# Sch.net
KiCad netlist of a schematic drawn in Altium Designer
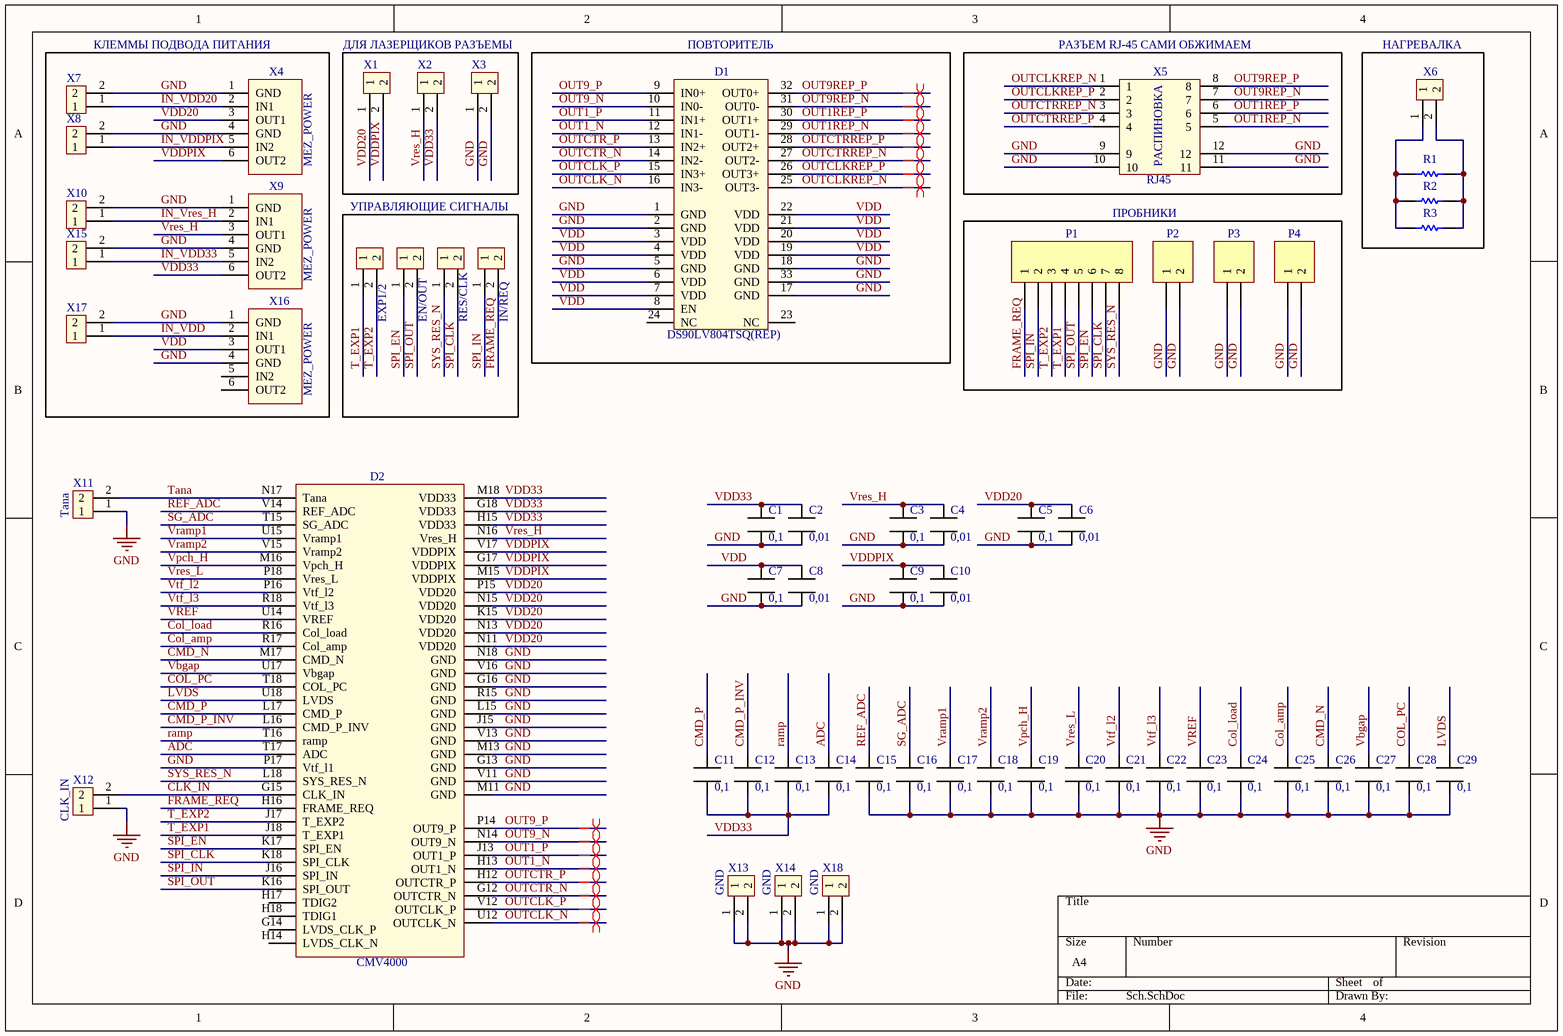
[diagram p0: Sch.SchDoc]

(export (version "E")
  (design (tool "Eeschema 10.0.6"))
  (components
    (comp (ref "C1") (value "0,1") (footprint "CAP_SMALL") (libsource (lib "Schlib") (part "CAP_SMALL")))
    (comp (ref "C2") (value "0,01") (footprint "CAP_SMALL") (libsource (lib "Schlib") (part "CAP_SMALL")))
    (comp (ref "C3") (value "0,1") (footprint "CAP_SMALL") (libsource (lib "Schlib") (part "CAP_SMALL")))
    (comp (ref "C4") (value "0,01") (footprint "CAP_SMALL") (libsource (lib "Schlib") (part "CAP_SMALL")))
    (comp (ref "C5") (value "0,1") (footprint "CAP_SMALL") (libsource (lib "Schlib") (part "CAP_SMALL")))
    (comp (ref "C6") (value "0,01") (footprint "CAP_SMALL") (libsource (lib "Schlib") (part "CAP_SMALL")))
    (comp (ref "C7") (value "0,1") (footprint "CAP_SMALL") (libsource (lib "Schlib") (part "CAP_SMALL")))
    (comp (ref "C8") (value "0,01") (footprint "CAP_SMALL") (libsource (lib "Schlib") (part "CAP_SMALL")))
    (comp (ref "C9") (value "0,1") (footprint "CAP_SMALL") (libsource (lib "Schlib") (part "CAP_SMALL")))
    (comp (ref "C10") (value "0,01") (footprint "CAP_SMALL") (libsource (lib "Schlib") (part "CAP_SMALL")))
    (comp (ref "C11") (value "0,1") (footprint "CAP_SMALL") (libsource (lib "Schlib") (part "CAP_SMALL")))
    (comp (ref "C12") (value "0,1") (footprint "CAP_SMALL") (libsource (lib "Schlib") (part "CAP_SMALL")))
    (comp (ref "C13") (value "0,1") (footprint "CAP_SMALL") (libsource (lib "Schlib") (part "CAP_SMALL")))
    (comp (ref "C14") (value "0,1") (footprint "CAP_SMALL") (libsource (lib "Schlib") (part "CAP_SMALL")))
    (comp (ref "C15") (value "0,1") (footprint "CAP_SMALL") (libsource (lib "Schlib") (part "CAP_SMALL")))
    (comp (ref "C16") (value "0,1") (footprint "CAP_SMALL") (libsource (lib "Schlib") (part "CAP_SMALL")))
    (comp (ref "C17") (value "0,1") (footprint "CAP_SMALL") (libsource (lib "Schlib") (part "CAP_SMALL")))
    (comp (ref "C18") (value "0,1") (footprint "CAP_SMALL") (libsource (lib "Schlib") (part "CAP_SMALL")))
    (comp (ref "C19") (value "0,1") (footprint "CAP_SMALL") (libsource (lib "Schlib") (part "CAP_SMALL")))
    (comp (ref "C20") (value "0,1") (footprint "CAP_SMALL") (libsource (lib "Schlib") (part "CAP_SMALL")))
    (comp (ref "C21") (value "0,1") (footprint "CAP_SMALL") (libsource (lib "Schlib") (part "CAP_SMALL")))
    (comp (ref "C22") (value "0,1") (footprint "CAP_SMALL") (libsource (lib "Schlib") (part "CAP_SMALL")))
    (comp (ref "C23") (value "0,1") (footprint "CAP_SMALL") (libsource (lib "Schlib") (part "CAP_SMALL")))
    (comp (ref "C24") (value "0,1") (footprint "CAP_SMALL") (libsource (lib "Schlib") (part "CAP_SMALL")))
    (comp (ref "C25") (value "0,1") (footprint "CAP_SMALL") (libsource (lib "Schlib") (part "CAP_SMALL")))
    (comp (ref "C26") (value "0,1") (footprint "CAP_SMALL") (libsource (lib "Schlib") (part "CAP_SMALL")))
    (comp (ref "C27") (value "0,1") (footprint "CAP_SMALL") (libsource (lib "Schlib") (part "CAP_SMALL")))
    (comp (ref "C28") (value "0,1") (footprint "CAP_SMALL") (libsource (lib "Schlib") (part "CAP_SMALL")))
    (comp (ref "C29") (value "0,1") (footprint "CAP_SMALL") (libsource (lib "Schlib") (part "CAP_SMALL")))
    (comp (ref "D1")
      (value "DS90LV804TSQ(REP)")
      (footprint "DS90LV804TSQ")
      (libsource (lib "Schlib") (part "DS90LV804TSQ"))
    )
    (comp (ref "D2") (value "CMV4000") (footprint "SOCKET_AM2") (libsource (lib "Schlib") (part "CMV4000")))
    (comp (ref "EN/OUT") (value "KL_2") (footprint "KLEMMNIK_2") (libsource (lib "") (part "KLEMMNIK_2_1")))
    (comp (ref "EXP1/2") (value "KL_2") (footprint "KLEMMNIK_2") (libsource (lib "") (part "KLEMMNIK_2_1")))
    (comp (ref "IN/REQ") (value "KL_2") (footprint "KLEMMNIK_2") (libsource (lib "") (part "KLEMMNIK_2_1")))
    (comp (ref "P1")
      (value "Header 8")
      (footprint "HDR1X8")
      (description "Header, 8-Pin")
      (fields (field (name "PUBLISHER") "Altium Limited"))
      (libsource (lib "Miscellaneous Connectors") (part "Header 8"))
    )
    (comp (ref "P2")
      (value "Header 2")
      (footprint "HDR1X2")
      (description "Header, 2-Pin")
      (fields (field (name "PUBLISHER") "Altium Limited"))
      (libsource (lib "Miscellaneous Connectors") (part "Header 2"))
    )
    (comp (ref "P3")
      (value "Header 2")
      (footprint "HDR1X2")
      (description "Header, 2-Pin")
      (fields (field (name "PUBLISHER") "Altium Limited"))
      (libsource (lib "Miscellaneous Connectors") (part "Header 2"))
    )
    (comp (ref "P4")
      (value "Header 2")
      (footprint "HDR1X2")
      (description "Header, 2-Pin")
      (fields (field (name "PUBLISHER") "Altium Limited"))
      (libsource (lib "Miscellaneous Connectors") (part "Header 2"))
    )
    (comp (ref "R1")
      (value "Res Semi")
      (footprint "AXIAL-0.5")
      (description "Semiconductor Resistor")
      (fields (field (name "PUBLISHER") "Altium Limited"))
      (libsource (lib "Miscellaneous Devices") (part "Res Semi"))
    )
    (comp (ref "R2")
      (value "Res Semi")
      (footprint "AXIAL-0.5")
      (description "Semiconductor Resistor")
      (fields (field (name "PUBLISHER") "Altium Limited"))
      (libsource (lib "Miscellaneous Devices") (part "Res Semi"))
    )
    (comp (ref "R3")
      (value "Res Semi")
      (footprint "AXIAL-0.5")
      (description "Semiconductor Resistor")
      (fields (field (name "PUBLISHER") "Altium Limited"))
      (libsource (lib "Miscellaneous Devices") (part "Res Semi"))
    )
    (comp (ref "RES/CLK") (value "KL_2") (footprint "KLEMMNIK_2") (libsource (lib "") (part "KLEMMNIK_2_1")))
    (comp (ref "X1") (value "KL_2") (footprint "KLEMMNIK_2") (libsource (lib "") (part "KLEMMNIK_2_1")))
    (comp (ref "X2") (value "KL_2") (footprint "KLEMMNIK_2") (libsource (lib "") (part "KLEMMNIK_2_1")))
    (comp (ref "X3") (value "KL_2") (footprint "KLEMMNIK_2") (libsource (lib "") (part "KLEMMNIK_2_1")))
    (comp (ref "X4")
      (value "MEZ_POWER")
      (footprint "MEZON_POWER_NEW")
      (libsource (lib "Schlib") (part "MEZON_POWER_NEW"))
    )
    (comp (ref "X5") (value "RJ45") (footprint "RJ45") (libsource (lib "Schlib") (part "RJ45")))
    (comp (ref "X6") (value "KL_2") (footprint "KLEMMNIK_2") (libsource (lib "") (part "KLEMMNIK_2_1")))
    (comp (ref "X7") (value "KL_2") (footprint "KLEMMNIK_2") (libsource (lib "Schlib") (part "KLEMMNIK_2")))
    (comp (ref "X8") (value "KL_2") (footprint "KLEMMNIK_2") (libsource (lib "Schlib") (part "KLEMMNIK_2")))
    (comp (ref "X9")
      (value "MEZ_POWER")
      (footprint "MEZON_POWER_NEW")
      (libsource (lib "Schlib") (part "MEZON_POWER_NEW"))
    )
    (comp (ref "X10") (value "KL_2") (footprint "KLEMMNIK_2") (libsource (lib "Schlib") (part "KLEMMNIK_2")))
    (comp (ref "X11") (value "Tana") (footprint "KLEMMNIK_2") (libsource (lib "Schlib") (part "KLEMMNIK_2")))
    (comp (ref "X12")
      (value "CLK_IN")
      (footprint "KLEMMNIK_2")
      (libsource (lib "Schlib") (part "KLEMMNIK_2"))
    )
    (comp (ref "X13") (value "GND") (footprint "KLEMMNIK_2") (libsource (lib "") (part "KLEMMNIK_2_1")))
    (comp (ref "X14") (value "GND") (footprint "KLEMMNIK_2") (libsource (lib "") (part "KLEMMNIK_2_1")))
    (comp (ref "X15") (value "KL_2") (footprint "KLEMMNIK_2") (libsource (lib "Schlib") (part "KLEMMNIK_2")))
    (comp (ref "X16")
      (value "MEZ_POWER")
      (footprint "MEZON_POWER_NEW")
      (libsource (lib "Schlib") (part "MEZON_POWER_NEW"))
    )
    (comp (ref "X17") (value "KL_2") (footprint "KLEMMNIK_2") (libsource (lib "Schlib") (part "KLEMMNIK_2")))
    (comp (ref "X18") (value "GND") (footprint "KLEMMNIK_2") (libsource (lib "") (part "KLEMMNIK_2_1")))
  )
  (nets
    (net (code "1") (name "/ADC") (class "Default")
      (node (ref "C14") (pin "2") (pinfunction "2_2") (pintype "passive"))
      (node (ref "D2") (pin "T17") (pinfunction "ADC_T17") (pintype "passive"))
    )
    (net (code "2") (name "/CLK_IN") (class "Default")
      (node (ref "D2") (pin "G15") (pinfunction "CLK_IN_G15") (pintype "passive"))
      (node (ref "X12") (pin "2") (pinfunction "2_2") (pintype "passive"))
    )
    (net (code "3") (name "/CMD_N") (class "Default")
      (node (ref "C26") (pin "2") (pinfunction "2_2") (pintype "passive"))
      (node (ref "D2") (pin "M17") (pinfunction "CMD_N_M17") (pintype "passive"))
    )
    (net (code "4") (name "/CMD_P") (class "Default")
      (node (ref "C11") (pin "2") (pinfunction "2_2") (pintype "passive"))
      (node (ref "D2") (pin "L17") (pinfunction "CMD_P_L17") (pintype "passive"))
    )
    (net (code "5") (name "/CMD_P_INV") (class "Default")
      (node (ref "C12") (pin "2") (pinfunction "2_2") (pintype "passive"))
      (node (ref "D2") (pin "L16") (pinfunction "CMD_P_INV_L16") (pintype "passive"))
    )
    (net (code "6") (name "/COL_PC") (class "Default")
      (node (ref "C28") (pin "2") (pinfunction "2_2") (pintype "passive"))
      (node (ref "D2") (pin "T18") (pinfunction "COL_PC_T18") (pintype "passive"))
    )
    (net (code "7") (name "/Col_amp") (class "Default")
      (node (ref "C25") (pin "2") (pinfunction "2_2") (pintype "passive"))
      (node (ref "D2") (pin "R17") (pinfunction "Col_amp_R17") (pintype "passive"))
    )
    (net (code "8") (name "/Col_load") (class "Default")
      (node (ref "C24") (pin "2") (pinfunction "2_2") (pintype "passive"))
      (node (ref "D2") (pin "R16") (pinfunction "Col_load_R16") (pintype "passive"))
    )
    (net (code "9") (name "/FRAME_REQ") (class "Default")
      (node (ref "D2") (pin "H16") (pinfunction "FRAME_REQ_H16") (pintype "passive"))
      (node (ref "IN/REQ") (pin "2") (pinfunction "2_2") (pintype "passive"))
      (node (ref "P1") (pin "1") (pinfunction "1_1") (pintype "passive"))
    )
    (net (code "10") (name "/IN_VDD") (class "Default")
      (node (ref "X16") (pin "2") (pinfunction "IN1_2") (pintype "passive"))
      (node (ref "X17") (pin "1") (pinfunction "1_1") (pintype "passive"))
    )
    (net (code "11") (name "/IN_VDD20") (class "Default")
      (node (ref "X4") (pin "2") (pinfunction "IN1_2") (pintype "passive"))
      (node (ref "X7") (pin "1") (pinfunction "1_1") (pintype "passive"))
    )
    (net (code "12") (name "/IN_VDD33") (class "Default")
      (node (ref "X15") (pin "1") (pinfunction "1_1") (pintype "passive"))
      (node (ref "X9") (pin "5") (pinfunction "IN2_5") (pintype "passive"))
    )
    (net (code "13") (name "/IN_VDDPIX") (class "Default")
      (node (ref "X4") (pin "5") (pinfunction "IN2_5") (pintype "passive"))
      (node (ref "X8") (pin "1") (pinfunction "1_1") (pintype "passive"))
    )
    (net (code "14") (name "/IN_Vres_H") (class "Default")
      (node (ref "X10") (pin "1") (pinfunction "1_1") (pintype "passive"))
      (node (ref "X9") (pin "2") (pinfunction "IN1_2") (pintype "passive"))
    )
    (net (code "15") (name "/LVDS") (class "Default")
      (node (ref "C29") (pin "2") (pinfunction "2_2") (pintype "passive"))
      (node (ref "D2") (pin "U18") (pinfunction "LVDS_U18") (pintype "passive"))
    )
    (net (code "16") (name "/OUT1REP_N") (class "Default")
      (node (ref "D1") (pin "29") (pinfunction "OUT1-_29") (pintype "passive"))
      (node (ref "X5") (pin "5") (pinfunction "5_5") (pintype "passive"))
    )
    (net (code "17") (name "/OUT1REP_P") (class "Default")
      (node (ref "D1") (pin "30") (pinfunction "OUT1+_30") (pintype "passive"))
      (node (ref "X5") (pin "6") (pinfunction "6_6") (pintype "passive"))
    )
    (net (code "18") (name "/OUT1_N") (class "Default")
      (node (ref "D1") (pin "12") (pinfunction "IN1-_12") (pintype "passive"))
      (node (ref "D2") (pin "H13") (pinfunction "OUT1_N_H13") (pintype "passive"))
    )
    (net (code "19") (name "/OUT1_P") (class "Default")
      (node (ref "D1") (pin "11") (pinfunction "IN1+_11") (pintype "passive"))
      (node (ref "D2") (pin "J13") (pinfunction "OUT1_P_J13") (pintype "passive"))
    )
    (net (code "20") (name "/OUT9REP_N") (class "Default")
      (node (ref "D1") (pin "31") (pinfunction "OUT0-_31") (pintype "passive"))
      (node (ref "X5") (pin "7") (pinfunction "7_7") (pintype "passive"))
    )
    (net (code "21") (name "/OUT9REP_P") (class "Default")
      (node (ref "D1") (pin "32") (pinfunction "OUT0+_32") (pintype "passive"))
      (node (ref "X5") (pin "8") (pinfunction "8_8") (pintype "passive"))
    )
    (net (code "22") (name "/OUT9_N") (class "Default")
      (node (ref "D1") (pin "10") (pinfunction "IN0-_10") (pintype "passive"))
      (node (ref "D2") (pin "N14") (pinfunction "OUT9_N_N14") (pintype "passive"))
    )
    (net (code "23") (name "/OUT9_P") (class "Default")
      (node (ref "D1") (pin "9") (pinfunction "IN0+_9") (pintype "passive"))
      (node (ref "D2") (pin "P14") (pinfunction "OUT9_P_P14") (pintype "passive"))
    )
    (net (code "24") (name "/OUTCLKREP_N") (class "Default")
      (node (ref "D1") (pin "25") (pinfunction "OUT3-_25") (pintype "passive"))
      (node (ref "X5") (pin "1") (pinfunction "1_1") (pintype "passive"))
    )
    (net (code "25") (name "/OUTCLKREP_P") (class "Default")
      (node (ref "D1") (pin "26") (pinfunction "OUT3+_26") (pintype "passive"))
      (node (ref "X5") (pin "2") (pinfunction "2_2") (pintype "passive"))
    )
    (net (code "26") (name "/OUTCLK_N") (class "Default")
      (node (ref "D1") (pin "16") (pinfunction "IN3-_16") (pintype "passive"))
      (node (ref "D2") (pin "U12") (pinfunction "OUTCLK_N_U12") (pintype "passive"))
    )
    (net (code "27") (name "/OUTCLK_P") (class "Default")
      (node (ref "D1") (pin "15") (pinfunction "IN3+_15") (pintype "passive"))
      (node (ref "D2") (pin "V12") (pinfunction "OUTCLK_P_V12") (pintype "passive"))
    )
    (net (code "28") (name "/OUTCTRREP_N") (class "Default")
      (node (ref "D1") (pin "27") (pinfunction "OUT2-_27") (pintype "passive"))
      (node (ref "X5") (pin "3") (pinfunction "3_3") (pintype "passive"))
    )
    (net (code "29") (name "/OUTCTRREP_P") (class "Default")
      (node (ref "D1") (pin "28") (pinfunction "OUT2+_28") (pintype "passive"))
      (node (ref "X5") (pin "4") (pinfunction "4_4") (pintype "passive"))
    )
    (net (code "30") (name "/OUTCTR_N") (class "Default")
      (node (ref "D1") (pin "14") (pinfunction "IN2-_14") (pintype "passive"))
      (node (ref "D2") (pin "G12") (pinfunction "OUTCTR_N_G12") (pintype "passive"))
    )
    (net (code "31") (name "/OUTCTR_P") (class "Default")
      (node (ref "D1") (pin "13") (pinfunction "IN2+_13") (pintype "passive"))
      (node (ref "D2") (pin "H12") (pinfunction "OUTCTR_P_H12") (pintype "passive"))
    )
    (net (code "32") (name "/REF_ADC") (class "Default")
      (node (ref "C15") (pin "2") (pinfunction "2_2") (pintype "passive"))
      (node (ref "D2") (pin "V14") (pinfunction "REF_ADC_V14") (pintype "passive"))
    )
    (net (code "33") (name "/SG_ADC") (class "Default")
      (node (ref "C16") (pin "2") (pinfunction "2_2") (pintype "passive"))
      (node (ref "D2") (pin "T15") (pinfunction "SG_ADC_T15") (pintype "passive"))
    )
    (net (code "34") (name "/SPI_CLK") (class "Default")
      (node (ref "D2") (pin "K18") (pinfunction "SPI_CLK_K18") (pintype "passive"))
      (node (ref "P1") (pin "7") (pinfunction "7_7") (pintype "passive"))
      (node (ref "RES/CLK") (pin "2") (pinfunction "2_2") (pintype "passive"))
    )
    (net (code "35") (name "/SPI_EN") (class "Default")
      (node (ref "D2") (pin "K17") (pinfunction "SPI_EN_K17") (pintype "passive"))
      (node (ref "EN/OUT") (pin "1") (pinfunction "1_1") (pintype "passive"))
      (node (ref "P1") (pin "6") (pinfunction "6_6") (pintype "passive"))
    )
    (net (code "36") (name "/SPI_IN") (class "Default")
      (node (ref "D2") (pin "J16") (pinfunction "SPI_IN_J16") (pintype "passive"))
      (node (ref "IN/REQ") (pin "1") (pinfunction "1_1") (pintype "passive"))
      (node (ref "P1") (pin "2") (pinfunction "2_2") (pintype "passive"))
    )
    (net (code "37") (name "/SPI_OUT") (class "Default")
      (node (ref "D2") (pin "K16") (pinfunction "SPI_OUT_K16") (pintype "passive"))
      (node (ref "EN/OUT") (pin "2") (pinfunction "2_2") (pintype "passive"))
      (node (ref "P1") (pin "5") (pinfunction "5_5") (pintype "passive"))
    )
    (net (code "38") (name "/SYS_RES_N") (class "Default")
      (node (ref "D2") (pin "L18") (pinfunction "SYS_RES_N_L18") (pintype "passive"))
      (node (ref "P1") (pin "8") (pinfunction "8_8") (pintype "passive"))
      (node (ref "RES/CLK") (pin "1") (pinfunction "1_1") (pintype "passive"))
    )
    (net (code "39") (name "/T_EXP1") (class "Default")
      (node (ref "D2") (pin "J18") (pinfunction "T_EXP1_J18") (pintype "passive"))
      (node (ref "EXP1/2") (pin "1") (pinfunction "1_1") (pintype "passive"))
      (node (ref "P1") (pin "4") (pinfunction "4_4") (pintype "passive"))
    )
    (net (code "40") (name "/T_EXP2") (class "Default")
      (node (ref "D2") (pin "J17") (pinfunction "T_EXP2_J17") (pintype "passive"))
      (node (ref "EXP1/2") (pin "2") (pinfunction "2_2") (pintype "passive"))
      (node (ref "P1") (pin "3") (pinfunction "3_3") (pintype "passive"))
    )
    (net (code "41") (name "/Tana") (class "Default")
      (node (ref "D2") (pin "N17") (pinfunction "Tana_N17") (pintype "passive"))
      (node (ref "X11") (pin "2") (pinfunction "2_2") (pintype "passive"))
    )
    (net (code "42") (name "/VDD") (class "Default")
      (node (ref "C7") (pin "2") (pinfunction "2_2") (pintype "passive"))
      (node (ref "C8") (pin "2") (pinfunction "2_2") (pintype "passive"))
      (node (ref "D1") (pin "19") (pinfunction "VDD_19") (pintype "passive"))
      (node (ref "D1") (pin "20") (pinfunction "VDD_20") (pintype "passive"))
      (node (ref "D1") (pin "21") (pinfunction "VDD_21") (pintype "passive"))
      (node (ref "D1") (pin "22") (pinfunction "VDD_22") (pintype "passive"))
      (node (ref "D1") (pin "3") (pinfunction "VDD_3") (pintype "passive"))
      (node (ref "D1") (pin "4") (pinfunction "VDD_4") (pintype "passive"))
      (node (ref "D1") (pin "6") (pinfunction "VDD_6") (pintype "passive"))
      (node (ref "D1") (pin "7") (pinfunction "VDD_7") (pintype "passive"))
      (node (ref "D1") (pin "8") (pinfunction "EN_8") (pintype "passive"))
      (node (ref "X16") (pin "3") (pinfunction "OUT1_3") (pintype "passive"))
    )
    (net (code "43") (name "/VDD20") (class "Default")
      (node (ref "C5") (pin "2") (pinfunction "2_2") (pintype "passive"))
      (node (ref "C6") (pin "2") (pinfunction "2_2") (pintype "passive"))
      (node (ref "D2") (pin "K15") (pinfunction "VDD20_K15") (pintype "passive"))
      (node (ref "D2") (pin "N11") (pinfunction "VDD20_N11") (pintype "passive"))
      (node (ref "D2") (pin "N13") (pinfunction "VDD20_N13") (pintype "passive"))
      (node (ref "D2") (pin "N15") (pinfunction "VDD20_N15") (pintype "passive"))
      (node (ref "D2") (pin "P15") (pinfunction "VDD20_P15") (pintype "passive"))
      (node (ref "X1") (pin "1") (pinfunction "1_1") (pintype "passive"))
      (node (ref "X4") (pin "3") (pinfunction "OUT1_3") (pintype "passive"))
    )
    (net (code "44") (name "/VDD33") (class "Default")
      (node (ref "C1") (pin "2") (pinfunction "2_2") (pintype "passive"))
      (node (ref "C11") (pin "1") (pinfunction "1_1") (pintype "passive"))
      (node (ref "C12") (pin "1") (pinfunction "1_1") (pintype "passive"))
      (node (ref "C13") (pin "1") (pinfunction "1_1") (pintype "passive"))
      (node (ref "C14") (pin "1") (pinfunction "1_1") (pintype "passive"))
      (node (ref "C2") (pin "2") (pinfunction "2_2") (pintype "passive"))
      (node (ref "D2") (pin "G18") (pinfunction "VDD33_G18") (pintype "passive"))
      (node (ref "D2") (pin "H15") (pinfunction "VDD33_H15") (pintype "passive"))
      (node (ref "D2") (pin "M18") (pinfunction "VDD33_M18") (pintype "passive"))
      (node (ref "X2") (pin "2") (pinfunction "2_2") (pintype "passive"))
      (node (ref "X9") (pin "6") (pinfunction "OUT2_6") (pintype "passive"))
    )
    (net (code "45") (name "/VDDPIX") (class "Default")
      (node (ref "C10") (pin "2") (pinfunction "2_2") (pintype "passive"))
      (node (ref "C9") (pin "2") (pinfunction "2_2") (pintype "passive"))
      (node (ref "D2") (pin "G17") (pinfunction "VDDPIX_G17") (pintype "passive"))
      (node (ref "D2") (pin "M15") (pinfunction "VDDPIX_M15") (pintype "passive"))
      (node (ref "D2") (pin "V17") (pinfunction "VDDPIX_V17") (pintype "passive"))
      (node (ref "X1") (pin "2") (pinfunction "2_2") (pintype "passive"))
      (node (ref "X4") (pin "6") (pinfunction "OUT2_6") (pintype "passive"))
    )
    (net (code "46") (name "/VREF") (class "Default")
      (node (ref "C23") (pin "2") (pinfunction "2_2") (pintype "passive"))
      (node (ref "D2") (pin "U14") (pinfunction "VREF_U14") (pintype "passive"))
    )
    (net (code "47") (name "/Vbgap") (class "Default")
      (node (ref "C27") (pin "2") (pinfunction "2_2") (pintype "passive"))
      (node (ref "D2") (pin "U17") (pinfunction "Vbgap_U17") (pintype "passive"))
    )
    (net (code "48") (name "/Vpch_H") (class "Default")
      (node (ref "C19") (pin "2") (pinfunction "2_2") (pintype "passive"))
      (node (ref "D2") (pin "M16") (pinfunction "Vpch_H_M16") (pintype "passive"))
    )
    (net (code "49") (name "/Vramp1") (class "Default")
      (node (ref "C17") (pin "2") (pinfunction "2_2") (pintype "passive"))
      (node (ref "D2") (pin "U15") (pinfunction "Vramp1_U15") (pintype "passive"))
    )
    (net (code "50") (name "/Vramp2") (class "Default")
      (node (ref "C18") (pin "2") (pinfunction "2_2") (pintype "passive"))
      (node (ref "D2") (pin "V15") (pinfunction "Vramp2_V15") (pintype "passive"))
    )
    (net (code "51") (name "/Vres_H") (class "Default")
      (node (ref "C3") (pin "2") (pinfunction "2_2") (pintype "passive"))
      (node (ref "C4") (pin "2") (pinfunction "2_2") (pintype "passive"))
      (node (ref "D2") (pin "N16") (pinfunction "Vres_H_N16") (pintype "passive"))
      (node (ref "X2") (pin "1") (pinfunction "1_1") (pintype "passive"))
      (node (ref "X9") (pin "3") (pinfunction "OUT1_3") (pintype "passive"))
    )
    (net (code "52") (name "/Vres_L") (class "Default")
      (node (ref "C20") (pin "2") (pinfunction "2_2") (pintype "passive"))
      (node (ref "D2") (pin "P18") (pinfunction "Vres_L_P18") (pintype "passive"))
    )
    (net (code "53") (name "/Vtf_l2") (class "Default")
      (node (ref "C21") (pin "2") (pinfunction "2_2") (pintype "passive"))
      (node (ref "D2") (pin "P16") (pinfunction "Vtf_l2_P16") (pintype "passive"))
    )
    (net (code "54") (name "/Vtf_l3") (class "Default")
      (node (ref "C22") (pin "2") (pinfunction "2_2") (pintype "passive"))
      (node (ref "D2") (pin "R18") (pinfunction "Vtf_l3_R18") (pintype "passive"))
    )
    (net (code "55") (name "/ramp") (class "Default")
      (node (ref "C13") (pin "2") (pinfunction "2_2") (pintype "passive"))
      (node (ref "D2") (pin "T16") (pinfunction "ramp_T16") (pintype "passive"))
    )
    (net (code "56") (name "GND") (class "Default")
      (node (ref "C1") (pin "1") (pinfunction "1_1") (pintype "passive"))
      (node (ref "C10") (pin "1") (pinfunction "1_1") (pintype "passive"))
      (node (ref "C15") (pin "1") (pinfunction "1_1") (pintype "passive"))
      (node (ref "C16") (pin "1") (pinfunction "1_1") (pintype "passive"))
      (node (ref "C17") (pin "1") (pinfunction "1_1") (pintype "passive"))
      (node (ref "C18") (pin "1") (pinfunction "1_1") (pintype "passive"))
      (node (ref "C19") (pin "1") (pinfunction "1_1") (pintype "passive"))
      (node (ref "C2") (pin "1") (pinfunction "1_1") (pintype "passive"))
      (node (ref "C20") (pin "1") (pinfunction "1_1") (pintype "passive"))
      (node (ref "C21") (pin "1") (pinfunction "1_1") (pintype "passive"))
      (node (ref "C22") (pin "1") (pinfunction "1_1") (pintype "passive"))
      (node (ref "C23") (pin "1") (pinfunction "1_1") (pintype "passive"))
      (node (ref "C24") (pin "1") (pinfunction "1_1") (pintype "passive"))
      (node (ref "C25") (pin "1") (pinfunction "1_1") (pintype "passive"))
      (node (ref "C26") (pin "1") (pinfunction "1_1") (pintype "passive"))
      (node (ref "C27") (pin "1") (pinfunction "1_1") (pintype "passive"))
      (node (ref "C28") (pin "1") (pinfunction "1_1") (pintype "passive"))
      (node (ref "C29") (pin "1") (pinfunction "1_1") (pintype "passive"))
      (node (ref "C3") (pin "1") (pinfunction "1_1") (pintype "passive"))
      (node (ref "C4") (pin "1") (pinfunction "1_1") (pintype "passive"))
      (node (ref "C5") (pin "1") (pinfunction "1_1") (pintype "passive"))
      (node (ref "C6") (pin "1") (pinfunction "1_1") (pintype "passive"))
      (node (ref "C7") (pin "1") (pinfunction "1_1") (pintype "passive"))
      (node (ref "C8") (pin "1") (pinfunction "1_1") (pintype "passive"))
      (node (ref "C9") (pin "1") (pinfunction "1_1") (pintype "passive"))
      (node (ref "D1") (pin "1") (pinfunction "GND_1") (pintype "passive"))
      (node (ref "D1") (pin "17") (pinfunction "GND_17") (pintype "passive"))
      (node (ref "D1") (pin "18") (pinfunction "GND_18") (pintype "passive"))
      (node (ref "D1") (pin "2") (pinfunction "GND_2") (pintype "passive"))
      (node (ref "D1") (pin "33") (pinfunction "GND_33") (pintype "passive"))
      (node (ref "D1") (pin "5") (pinfunction "GND_5") (pintype "passive"))
      (node (ref "D2") (pin "G13") (pinfunction "GND_G13") (pintype "passive"))
      (node (ref "D2") (pin "G16") (pinfunction "GND_G16") (pintype "passive"))
      (node (ref "D2") (pin "J15") (pinfunction "GND_J15") (pintype "passive"))
      (node (ref "D2") (pin "L15") (pinfunction "GND_L15") (pintype "passive"))
      (node (ref "D2") (pin "M11") (pinfunction "GND_M11") (pintype "passive"))
      (node (ref "D2") (pin "M13") (pinfunction "GND_M13") (pintype "passive"))
      (node (ref "D2") (pin "N18") (pinfunction "GND_N18") (pintype "passive"))
      (node (ref "D2") (pin "P17") (pinfunction "Vtf_l1_P17") (pintype "passive"))
      (node (ref "D2") (pin "R15") (pinfunction "GND_R15") (pintype "passive"))
      (node (ref "D2") (pin "V11") (pinfunction "GND_V11") (pintype "passive"))
      (node (ref "D2") (pin "V13") (pinfunction "GND_V13") (pintype "passive"))
      (node (ref "D2") (pin "V16") (pinfunction "GND_V16") (pintype "passive"))
      (node (ref "P2") (pin "1") (pinfunction "1_1") (pintype "passive"))
      (node (ref "P2") (pin "2") (pinfunction "2_2") (pintype "passive"))
      (node (ref "P3") (pin "1") (pinfunction "1_1") (pintype "passive"))
      (node (ref "P3") (pin "2") (pinfunction "2_2") (pintype "passive"))
      (node (ref "P4") (pin "1") (pinfunction "1_1") (pintype "passive"))
      (node (ref "P4") (pin "2") (pinfunction "2_2") (pintype "passive"))
      (node (ref "X10") (pin "2") (pinfunction "2_2") (pintype "passive"))
      (node (ref "X11") (pin "1") (pinfunction "1_1") (pintype "passive"))
      (node (ref "X12") (pin "1") (pinfunction "1_1") (pintype "passive"))
      (node (ref "X13") (pin "1") (pinfunction "1_1") (pintype "passive"))
      (node (ref "X13") (pin "2") (pinfunction "2_2") (pintype "passive"))
      (node (ref "X14") (pin "1") (pinfunction "1_1") (pintype "passive"))
      (node (ref "X14") (pin "2") (pinfunction "2_2") (pintype "passive"))
      (node (ref "X15") (pin "2") (pinfunction "2_2") (pintype "passive"))
      (node (ref "X16") (pin "1") (pinfunction "GND_1") (pintype "passive"))
      (node (ref "X16") (pin "4") (pinfunction "GND_4") (pintype "passive"))
      (node (ref "X17") (pin "2") (pinfunction "2_2") (pintype "passive"))
      (node (ref "X18") (pin "1") (pinfunction "1_1") (pintype "passive"))
      (node (ref "X18") (pin "2") (pinfunction "2_2") (pintype "passive"))
      (node (ref "X3") (pin "1") (pinfunction "1_1") (pintype "passive"))
      (node (ref "X3") (pin "2") (pinfunction "2_2") (pintype "passive"))
      (node (ref "X4") (pin "1") (pinfunction "GND_1") (pintype "passive"))
      (node (ref "X4") (pin "4") (pinfunction "GND_4") (pintype "passive"))
      (node (ref "X5") (pin "10") (pinfunction "10_10") (pintype "passive"))
      (node (ref "X5") (pin "11") (pinfunction "11_11") (pintype "passive"))
      (node (ref "X5") (pin "12") (pinfunction "12_12") (pintype "passive"))
      (node (ref "X5") (pin "9") (pinfunction "9_9") (pintype "passive"))
      (node (ref "X7") (pin "2") (pinfunction "2_2") (pintype "passive"))
      (node (ref "X8") (pin "2") (pinfunction "2_2") (pintype "passive"))
      (node (ref "X9") (pin "1") (pinfunction "GND_1") (pintype "passive"))
      (node (ref "X9") (pin "4") (pinfunction "GND_4") (pintype "passive"))
    )
    (net (code "57") (name "Net-(R1-Pad1)") (class "Default")
      (node (ref "R1") (pin "1") (pinfunction "1_1") (pintype "passive"))
      (node (ref "R2") (pin "1") (pinfunction "1_1") (pintype "passive"))
      (node (ref "R3") (pin "1") (pinfunction "1_1") (pintype "passive"))
      (node (ref "X6") (pin "1") (pinfunction "1_1") (pintype "passive"))
    )
    (net (code "58") (name "Net-(R1-Pad2)") (class "Default")
      (node (ref "R1") (pin "2") (pinfunction "2_2") (pintype "passive"))
      (node (ref "R2") (pin "2") (pinfunction "2_2") (pintype "passive"))
      (node (ref "R3") (pin "2") (pinfunction "2_2") (pintype "passive"))
      (node (ref "X6") (pin "2") (pinfunction "2_2") (pintype "passive"))
    )
    (net (code "59") (name "unconnected-(D1-NC-Pad23)") (class "Default")
      (node (ref "D1") (pin "23") (pinfunction "NC_23") (pintype "passive"))
    )
    (net (code "60") (name "unconnected-(D1-NC-Pad24)") (class "Default")
      (node (ref "D1") (pin "24") (pinfunction "NC_24") (pintype "passive"))
    )
    (net (code "61") (name "unconnected-(D2-LVDS_CLK_N-PadH14)") (class "Default")
      (node (ref "D2") (pin "H14") (pinfunction "LVDS_CLK_N_H14") (pintype "passive"))
    )
    (net (code "62") (name "unconnected-(D2-LVDS_CLK_P-PadG14)") (class "Default")
      (node (ref "D2") (pin "G14") (pinfunction "LVDS_CLK_P_G14") (pintype "passive"))
    )
    (net (code "63") (name "unconnected-(D2-TDIG1-PadH18)") (class "Default")
      (node (ref "D2") (pin "H18") (pinfunction "TDIG1_H18") (pintype "passive"))
    )
    (net (code "64") (name "unconnected-(D2-TDIG2-PadH17)") (class "Default")
      (node (ref "D2") (pin "H17") (pinfunction "TDIG2_H17") (pintype "passive"))
    )
    (net (code "65") (name "unconnected-(X16-IN2-Pad5)") (class "Default")
      (node (ref "X16") (pin "5") (pinfunction "IN2_5") (pintype "passive"))
    )
    (net (code "66") (name "unconnected-(X16-OUT2-Pad6)") (class "Default")
      (node (ref "X16") (pin "6") (pinfunction "OUT2_6") (pintype "passive"))
    )
  )
)
